# base_module_e1_0_2.net
KiCad netlist of a schematic drawn in EAGLE
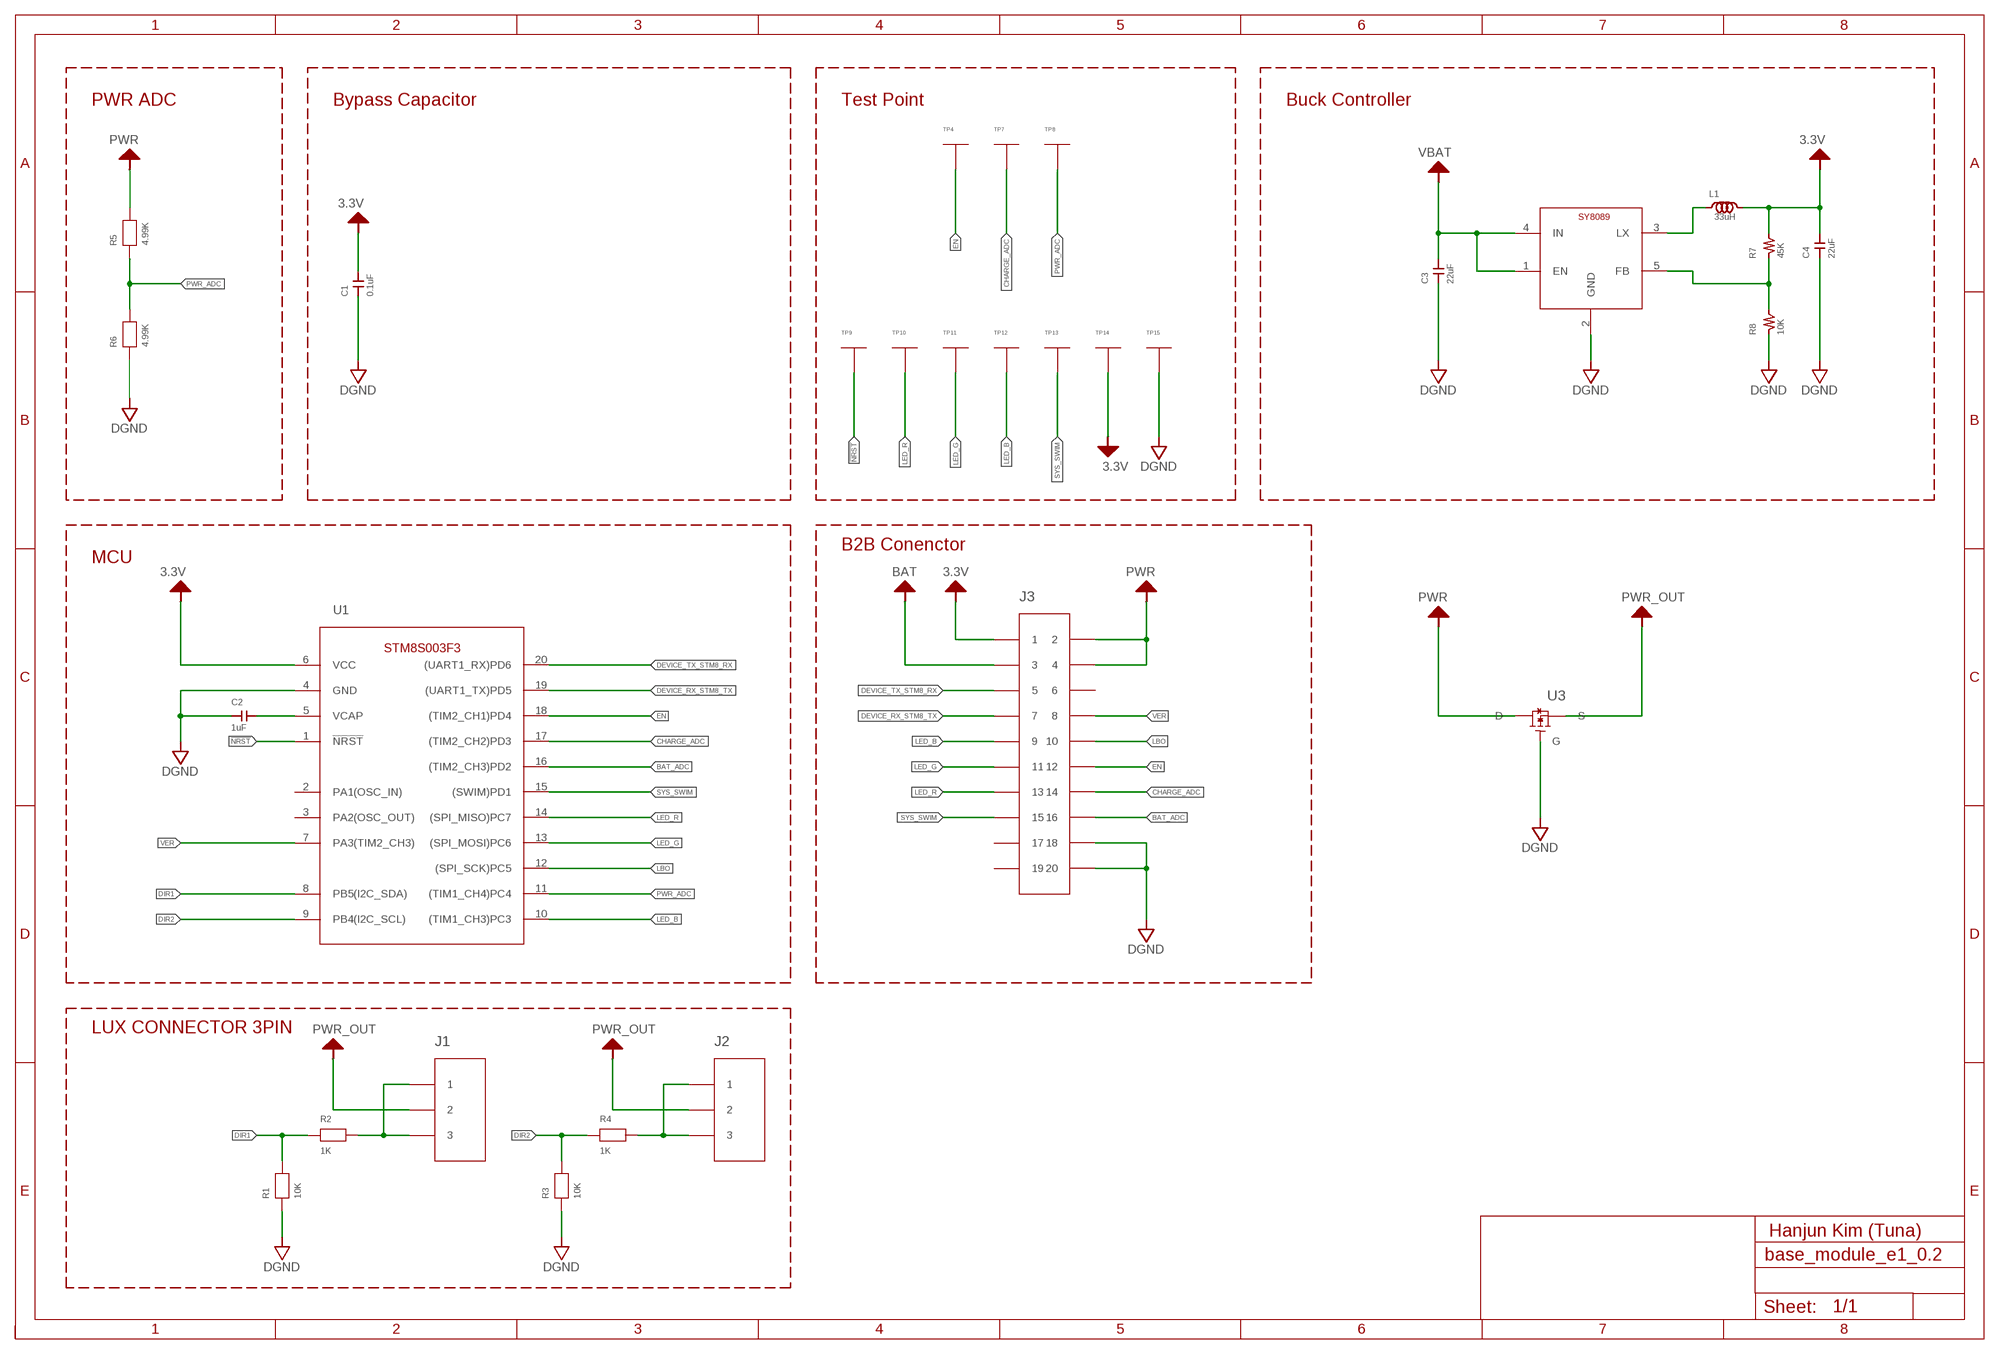
[diagram p0: schematic, sheet 1]

(export (version "E")
  (design (tool "Eeschema 10.0.6"))
  (components
    (comp (ref "C1")
      (value "0.1uF")
      (footprint "eagle-import:1005")
      (libsource (lib "eagle-import") (part "CAPACITOR_CHIP1005"))
    )
    (comp (ref "C2")
      (value "1uF")
      (footprint "eagle-import:1005")
      (libsource (lib "eagle-import") (part "CAPACITOR_CHIP1005"))
    )
    (comp (ref "C3")
      (value "22uF")
      (footprint "eagle-import:1608")
      (libsource (lib "eagle-import") (part "CAPACITOR_CHIP1608"))
    )
    (comp (ref "C4")
      (value "22uF")
      (footprint "eagle-import:1608")
      (libsource (lib "eagle-import") (part "CAPACITOR_CHIP1608"))
    )
    (comp (ref "J1")
      (value "MODI_CONNECTOR_BOTTOM")
      (footprint "eagle-import:3P")
      (libsource (lib "eagle-import") (part "MODI_CONNECTOR_BOTTOM"))
    )
    (comp (ref "J2")
      (value "MODI_CONNECTOR_BOTTOM")
      (footprint "eagle-import:3P")
      (libsource (lib "eagle-import") (part "MODI_CONNECTOR_BOTTOM"))
    )
    (comp (ref "J3")
      (value "AXK720447G")
      (footprint "eagle-import:SOCKET_20P")
      (libsource (lib "eagle-import") (part "AXK720447G"))
    )
    (comp (ref "L1")
      (value "33uH")
      (footprint "eagle-import:2518")
      (libsource (lib "eagle-import") (part "INDUCTOR2518"))
    )
    (comp (ref "LOGO1")
      (value "LOGO_LUXROBO_PCB")
      (footprint "eagle-import:PCB_LUXROBO_6.5X2.5")
      (libsource (lib "eagle-import") (part "LOGO_LUXROBO_PCB"))
    )
    (comp (ref "LOGO2")
      (value "LOGO_MODI_PCB6.5X2.5")
      (footprint "eagle-import:PCB_MODI_6.5X2.5")
      (libsource (lib "eagle-import") (part "LOGO_MODI_PCB6.5X2.5"))
    )
    (comp (ref "P1")
      (value "MODI_BAT_BASE")
      (footprint "eagle-import:BAT_BASE")
      (libsource (lib "eagle-import") (part "MODI_BAT_BASE"))
    )
    (comp (ref "R1")
      (value "10K")
      (footprint "eagle-import:1005")
      (libsource (lib "eagle-import") (part "RESISTOR_CHIP_SMALL1005"))
    )
    (comp (ref "R2")
      (value "1K")
      (footprint "eagle-import:1005")
      (libsource (lib "eagle-import") (part "RESISTOR_CHIP_SMALL1005"))
    )
    (comp (ref "R3")
      (value "10K")
      (footprint "eagle-import:1005")
      (libsource (lib "eagle-import") (part "RESISTOR_CHIP_SMALL1005"))
    )
    (comp (ref "R4")
      (value "1K")
      (footprint "eagle-import:1005")
      (libsource (lib "eagle-import") (part "RESISTOR_CHIP_SMALL1005"))
    )
    (comp (ref "R5")
      (value "4.99K")
      (footprint "eagle-import:1005")
      (libsource (lib "eagle-import") (part "RESISTOR_CHIP_SMALL1005"))
    )
    (comp (ref "R6")
      (value "4.99K")
      (footprint "eagle-import:1005")
      (libsource (lib "eagle-import") (part "RESISTOR_CHIP_SMALL1005"))
    )
    (comp (ref "R7")
      (value "45K")
      (footprint "eagle-import:1005")
      (libsource (lib "eagle-import") (part "RESISTOR_CHIP_1005"))
    )
    (comp (ref "R8")
      (value "10K")
      (footprint "eagle-import:1005")
      (libsource (lib "eagle-import") (part "RESISTOR_CHIP_1005"))
    )
    (comp (ref "TP4")
      (value "TEST_POINT_1.2MM_PAD")
      (footprint "eagle-import:1.2MM_PAD")
      (libsource (lib "eagle-import") (part "TEST_POINT_1.2MM_PAD"))
    )
    (comp (ref "TP7")
      (value "TEST_POINT_1.2MM_PAD")
      (footprint "eagle-import:1.2MM_PAD")
      (libsource (lib "eagle-import") (part "TEST_POINT_1.2MM_PAD"))
    )
    (comp (ref "TP8")
      (value "TEST_POINT_1.2MM_PAD")
      (footprint "eagle-import:1.2MM_PAD")
      (libsource (lib "eagle-import") (part "TEST_POINT_1.2MM_PAD"))
    )
    (comp (ref "TP9")
      (value "TEST_POINT_1.2MM_PAD")
      (footprint "eagle-import:1.2MM_PAD")
      (libsource (lib "eagle-import") (part "TEST_POINT_1.2MM_PAD"))
    )
    (comp (ref "TP10")
      (value "TEST_POINT_1.2MM_PAD")
      (footprint "eagle-import:1.2MM_PAD")
      (libsource (lib "eagle-import") (part "TEST_POINT_1.2MM_PAD"))
    )
    (comp (ref "TP11")
      (value "TEST_POINT_1.2MM_PAD")
      (footprint "eagle-import:1.2MM_PAD")
      (libsource (lib "eagle-import") (part "TEST_POINT_1.2MM_PAD"))
    )
    (comp (ref "TP12")
      (value "TEST_POINT_1.2MM_PAD")
      (footprint "eagle-import:1.2MM_PAD")
      (libsource (lib "eagle-import") (part "TEST_POINT_1.2MM_PAD"))
    )
    (comp (ref "TP13")
      (value "TEST_POINT")
      (footprint "eagle-import:0.7MM_HOLE")
      (libsource (lib "eagle-import") (part "TEST_POINT"))
    )
    (comp (ref "TP14")
      (value "TEST_POINT")
      (footprint "eagle-import:0.7MM_HOLE")
      (libsource (lib "eagle-import") (part "TEST_POINT"))
    )
    (comp (ref "TP15")
      (value "TEST_POINT")
      (footprint "eagle-import:0.7MM_HOLE")
      (libsource (lib "eagle-import") (part "TEST_POINT"))
    )
    (comp (ref "U1")
      (value "STM8S003FXU6")
      (footprint "eagle-import:UFQFPN20")
      (libsource (lib "eagle-import") (part "STM8S003FXU6"))
    )
    (comp (ref "U2")
      (value "SY8089")
      (footprint "eagle-import:SOT-23-5")
      (libsource (lib "eagle-import") (part "SY8089"))
    )
    (comp (ref "U3")
      (value "PMXBXXXXPE")
      (footprint "eagle-import:DFN1010D-3")
      (libsource (lib "eagle-import") (part "PMXBXXXXPE"))
    )
  )
  (nets
    (net (code "1") (name "/~{NRST}") (class "Default")
      (node (ref "TP9") (pin "P1") (pinfunction "P$1_P1") (pintype "bidirectional"))
      (node (ref "U1") (pin "1") (pinfunction "~{NRST}_1") (pintype "bidirectional"))
    )
    (net (code "2") (name "3.3V") (class "Default")
      (node (ref "C1") (pin "P$2") (pinfunction "P$2_P$2") (pintype "passive"))
      (node (ref "C4") (pin "P$2") (pinfunction "P$2_P$2") (pintype "passive"))
      (node (ref "J3") (pin "P1") (pinfunction "1_P1") (pintype "bidirectional"))
      (node (ref "L1") (pin "P$2") (pinfunction "P$2_P$2") (pintype "passive"))
      (node (ref "R7") (pin "P$2") (pinfunction "P$2_P$2") (pintype "passive"))
      (node (ref "TP14") (pin "1") (pinfunction "P$1_1") (pintype "bidirectional"))
      (node (ref "U1") (pin "6") (pinfunction "VCC_6") (pintype "power_in"))
    )
    (net (code "3") (name "BAT") (class "Default")
      (node (ref "C3") (pin "P$2") (pinfunction "P$2_P$2") (pintype "passive"))
      (node (ref "J3") (pin "P3") (pinfunction "3_P3") (pintype "bidirectional"))
      (node (ref "U2") (pin "1") (pinfunction "EN_1") (pintype "bidirectional"))
      (node (ref "U2") (pin "4") (pinfunction "IN_4") (pintype "input"))
    )
    (net (code "4") (name "BAT_ADC") (class "Default")
      (node (ref "J3") (pin "P16") (pinfunction "16_P16") (pintype "bidirectional"))
      (node (ref "U1") (pin "16") (pinfunction "(TIM2_CH3)PD2_16") (pintype "bidirectional"))
    )
    (net (code "5") (name "CHARGE_ADC") (class "Default")
      (node (ref "J3") (pin "P14") (pinfunction "14_P14") (pintype "bidirectional"))
      (node (ref "TP7") (pin "P1") (pinfunction "P$1_P1") (pintype "bidirectional"))
      (node (ref "U1") (pin "17") (pinfunction "(TIM2_CH2)PD3_17") (pintype "bidirectional"))
    )
    (net (code "6") (name "DEVICE_RX_STM8_TX") (class "Default")
      (node (ref "J3") (pin "P7") (pinfunction "7_P7") (pintype "bidirectional"))
      (node (ref "U1") (pin "19") (pinfunction "(UART1_TX)PD5_19") (pintype "bidirectional"))
    )
    (net (code "7") (name "DEVICE_TX_STM8_RX") (class "Default")
      (node (ref "J3") (pin "P5") (pinfunction "5_P5") (pintype "bidirectional"))
      (node (ref "U1") (pin "20") (pinfunction "(UART1_RX)PD6_20") (pintype "bidirectional"))
    )
    (net (code "8") (name "DGND") (class "Default")
      (node (ref "C1") (pin "P$1") (pinfunction "P$1_P$1") (pintype "passive"))
      (node (ref "C2") (pin "P$1") (pinfunction "P$1_P$1") (pintype "passive"))
      (node (ref "C3") (pin "P$1") (pinfunction "P$1_P$1") (pintype "passive"))
      (node (ref "C4") (pin "P$1") (pinfunction "P$1_P$1") (pintype "passive"))
      (node (ref "J3") (pin "P18") (pinfunction "18_P18") (pintype "bidirectional"))
      (node (ref "J3") (pin "P20") (pinfunction "20_P20") (pintype "bidirectional"))
      (node (ref "R1") (pin "P$1") (pinfunction "P$1_P$1") (pintype "bidirectional"))
      (node (ref "R3") (pin "P$1") (pinfunction "P$1_P$1") (pintype "bidirectional"))
      (node (ref "R6") (pin "P$1") (pinfunction "P$1_P$1") (pintype "bidirectional"))
      (node (ref "R8") (pin "P$1") (pinfunction "P$1_P$1") (pintype "passive"))
      (node (ref "TP15") (pin "1") (pinfunction "P$1_1") (pintype "bidirectional"))
      (node (ref "U1") (pin "4") (pinfunction "GND_4") (pintype "power_in"))
      (node (ref "U2") (pin "2") (pinfunction "GND_2") (pintype "power_in"))
      (node (ref "U3") (pin "P1") (pinfunction "G_P1") (pintype "bidirectional"))
    )
    (net (code "9") (name "DIR1") (class "Default")
      (node (ref "R1") (pin "P$2") (pinfunction "P$2_P$2") (pintype "bidirectional"))
      (node (ref "R2") (pin "P$1") (pinfunction "P$1_P$1") (pintype "bidirectional"))
      (node (ref "U1") (pin "8") (pinfunction "PB5(I2C_SDA)_8") (pintype "bidirectional"))
    )
    (net (code "10") (name "DIR2") (class "Default")
      (node (ref "R3") (pin "P$2") (pinfunction "P$2_P$2") (pintype "bidirectional"))
      (node (ref "R4") (pin "P$1") (pinfunction "P$1_P$1") (pintype "bidirectional"))
      (node (ref "U1") (pin "9") (pinfunction "PB4(I2C_SCL)_9") (pintype "bidirectional"))
    )
    (net (code "11") (name "EN") (class "Default")
      (node (ref "J3") (pin "P12") (pinfunction "12_P12") (pintype "bidirectional"))
      (node (ref "TP4") (pin "P1") (pinfunction "P$1_P1") (pintype "bidirectional"))
      (node (ref "U1") (pin "18") (pinfunction "(TIM2_CH1)PD4_18") (pintype "bidirectional"))
    )
    (net (code "12") (name "LBO") (class "Default")
      (node (ref "J3") (pin "P10") (pinfunction "10_P10") (pintype "bidirectional"))
      (node (ref "U1") (pin "12") (pinfunction "(SPI_SCK)PC5_12") (pintype "bidirectional"))
    )
    (net (code "13") (name "LED_B") (class "Default")
      (node (ref "J3") (pin "P9") (pinfunction "9_P9") (pintype "bidirectional"))
      (node (ref "TP12") (pin "P1") (pinfunction "P$1_P1") (pintype "bidirectional"))
      (node (ref "U1") (pin "10") (pinfunction "(TIM1_CH3)PC3_10") (pintype "bidirectional"))
    )
    (net (code "14") (name "LED_G") (class "Default")
      (node (ref "J3") (pin "P11") (pinfunction "11_P11") (pintype "bidirectional"))
      (node (ref "TP11") (pin "P1") (pinfunction "P$1_P1") (pintype "bidirectional"))
      (node (ref "U1") (pin "13") (pinfunction "(SPI_MOSI)PC6_13") (pintype "bidirectional"))
    )
    (net (code "15") (name "LED_R") (class "Default")
      (node (ref "J3") (pin "P13") (pinfunction "13_P13") (pintype "bidirectional"))
      (node (ref "TP10") (pin "P1") (pinfunction "P$1_P1") (pintype "bidirectional"))
      (node (ref "U1") (pin "14") (pinfunction "(SPI_MISO)PC7_14") (pintype "bidirectional"))
    )
    (net (code "16") (name "Net-(J1-1)") (class "Default")
      (node (ref "J1") (pin "P1") (pinfunction "1_P1") (pintype "bidirectional"))
      (node (ref "J1") (pin "P3") (pinfunction "3_P3") (pintype "bidirectional"))
      (node (ref "R2") (pin "P$2") (pinfunction "P$2_P$2") (pintype "bidirectional"))
    )
    (net (code "17") (name "Net-(J2-1)") (class "Default")
      (node (ref "J2") (pin "P1") (pinfunction "1_P1") (pintype "bidirectional"))
      (node (ref "J2") (pin "P3") (pinfunction "3_P3") (pintype "bidirectional"))
      (node (ref "R4") (pin "P$2") (pinfunction "P$2_P$2") (pintype "bidirectional"))
    )
    (net (code "18") (name "Net-(U1-VCAP)") (class "Default")
      (node (ref "C2") (pin "P$2") (pinfunction "P$2_P$2") (pintype "passive"))
      (node (ref "U1") (pin "5") (pinfunction "VCAP_5") (pintype "power_in"))
    )
    (net (code "19") (name "Net-(U2-FB)") (class "Default")
      (node (ref "R7") (pin "P$1") (pinfunction "P$1_P$1") (pintype "passive"))
      (node (ref "R8") (pin "P$2") (pinfunction "P$2_P$2") (pintype "passive"))
      (node (ref "U2") (pin "5") (pinfunction "FB_5") (pintype "power_in"))
    )
    (net (code "20") (name "Net-(U2-LX)") (class "Default")
      (node (ref "L1") (pin "P$1") (pinfunction "P$1_P$1") (pintype "passive"))
      (node (ref "U2") (pin "3") (pinfunction "LX_3") (pintype "bidirectional"))
    )
    (net (code "21") (name "PWR") (class "Default")
      (node (ref "J3") (pin "P2") (pinfunction "2_P2") (pintype "bidirectional"))
      (node (ref "J3") (pin "P4") (pinfunction "4_P4") (pintype "bidirectional"))
      (node (ref "R5") (pin "P$2") (pinfunction "P$2_P$2") (pintype "bidirectional"))
      (node (ref "U3") (pin "P3") (pinfunction "D_P3") (pintype "bidirectional"))
    )
    (net (code "22") (name "PWR_ADC") (class "Default")
      (node (ref "R5") (pin "P$1") (pinfunction "P$1_P$1") (pintype "bidirectional"))
      (node (ref "R6") (pin "P$2") (pinfunction "P$2_P$2") (pintype "bidirectional"))
      (node (ref "TP8") (pin "P1") (pinfunction "P$1_P1") (pintype "bidirectional"))
      (node (ref "U1") (pin "11") (pinfunction "(TIM1_CH4)PC4_11") (pintype "bidirectional"))
    )
    (net (code "23") (name "PWR_OUT") (class "Default")
      (node (ref "J1") (pin "P2") (pinfunction "2_P2") (pintype "bidirectional"))
      (node (ref "J2") (pin "P2") (pinfunction "2_P2") (pintype "bidirectional"))
      (node (ref "U3") (pin "P2") (pinfunction "S_P2") (pintype "bidirectional"))
    )
    (net (code "24") (name "SYS_SWIM") (class "Default")
      (node (ref "J3") (pin "P15") (pinfunction "15_P15") (pintype "bidirectional"))
      (node (ref "TP13") (pin "1") (pinfunction "P$1_1") (pintype "bidirectional"))
      (node (ref "U1") (pin "15") (pinfunction "(SWIM)PD1_15") (pintype "bidirectional"))
    )
    (net (code "25") (name "VER") (class "Default")
      (node (ref "J3") (pin "P8") (pinfunction "8_P8") (pintype "bidirectional"))
      (node (ref "U1") (pin "7") (pinfunction "PA3(TIM2_CH3)_7") (pintype "bidirectional"))
    )
    (net (code "26") (name "unconnected-(J3-6-PadP6)") (class "Default")
      (node (ref "J3") (pin "P6") (pinfunction "6_P6") (pintype "bidirectional"))
    )
    (net (code "27") (name "unconnected-(J3-17-PadP17)") (class "Default")
      (node (ref "J3") (pin "P17") (pinfunction "17_P17") (pintype "bidirectional"))
    )
    (net (code "28") (name "unconnected-(J3-19-PadP19)") (class "Default")
      (node (ref "J3") (pin "P19") (pinfunction "19_P19") (pintype "bidirectional"))
    )
    (net (code "29") (name "unconnected-(U1-PA1(OSC_IN)-Pad2)") (class "Default")
      (node (ref "U1") (pin "2") (pinfunction "PA1(OSC_IN)_2") (pintype "bidirectional"))
    )
    (net (code "30") (name "unconnected-(U1-PA2(OSC_OUT)-Pad3)") (class "Default")
      (node (ref "U1") (pin "3") (pinfunction "PA2(OSC_OUT)_3") (pintype "bidirectional"))
    )
  )
)
